# Drone_v1_0.net
KiCad netlist of a schematic drawn in Altium Designer
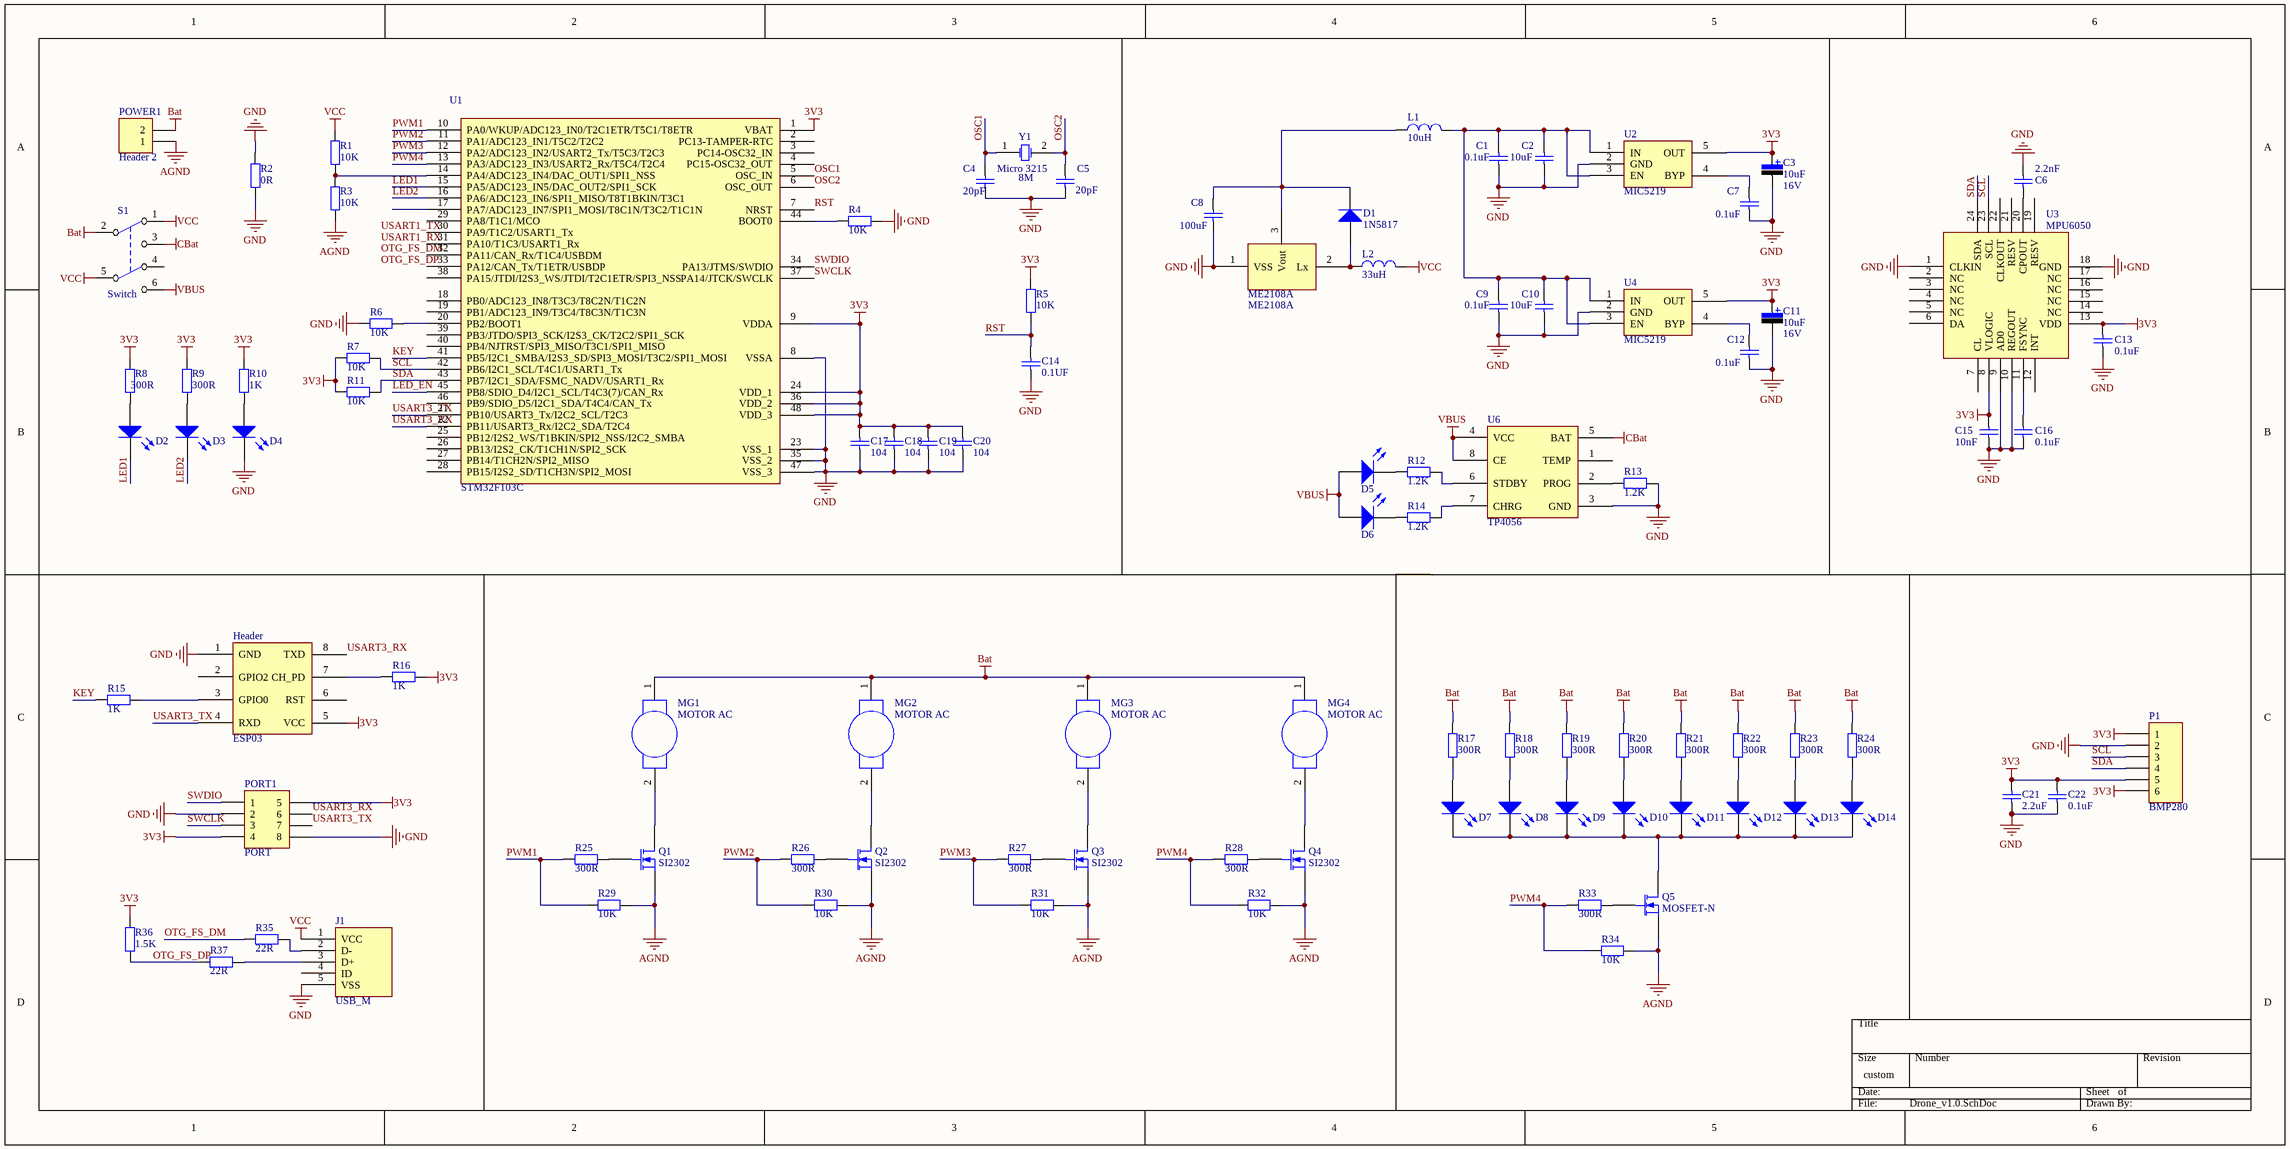
[diagram p0: Drone_v1.0.SchDoc]

(export (version "E")
  (design (tool "Eeschema 10.0.6"))
  (components
    (comp (ref "C1")
      (value "0.1uF")
      (footprint "0805-2")
      (description "Capacitor")
      (fields (field (name "Comment") "0402 12pF") (field (name "PUBLISHER") "Altium Limited"))
      (libsource (lib "Miscellaneous Devices") (part "Cap"))
    )
    (comp (ref "C2")
      (value "10uF")
      (footprint "0805-2")
      (description "Capacitor")
      (fields (field (name "Comment") "0402 12pF") (field (name "PUBLISHER") "Altium Limited"))
      (libsource (lib "Miscellaneous Devices") (part "Cap"))
    )
    (comp (ref "C3")
      (value "10uF")
      (footprint "CAP-3528")
      (description "极性电解电容")
      (fields
        (field (name "VOL") "16V")
        (field (name "Comment") "Cap Pol")
        (field (name "PUBLISHER") "Altium Limited")
      )
      (libsource (lib "Fszhang") (part "Cap Pol"))
    )
    (comp (ref "C4")
      (value "20pF")
      (footprint "0805-2")
      (description "Capacitor")
      (fields (field (name "Comment") "0402 12pF") (field (name "PUBLISHER") "Altium Limited"))
      (libsource (lib "Miscellaneous Devices") (part "Cap"))
    )
    (comp (ref "C5")
      (value "20pF")
      (footprint "0805-2")
      (description "Capacitor")
      (fields (field (name "Comment") "0402 12pF") (field (name "PUBLISHER") "Altium Limited"))
      (libsource (lib "Miscellaneous Devices") (part "Cap"))
    )
    (comp (ref "C6")
      (value "0402 12pF")
      (footprint "0805-2")
      (description "Capacitor")
      (fields (field (name "50V") "2.2nF") (field (name "PUBLISHER") "Altium Limited"))
      (libsource (lib "Miscellaneous Devices") (part "Cap"))
    )
    (comp (ref "C7")
      (value "0402 12pF")
      (footprint "0805-2")
      (description "Capacitor")
      (fields (field (name "50V") "0.1uF") (field (name "PUBLISHER") "Altium Limited"))
      (libsource (lib "Miscellaneous Devices") (part "Cap"))
    )
    (comp (ref "C8")
      (value "100uF")
      (footprint "0805-2")
      (description "Capacitor")
      (fields (field (name "Comment") "0402 12pF") (field (name "PUBLISHER") "Altium Limited"))
      (libsource (lib "Miscellaneous Devices") (part "Cap"))
    )
    (comp (ref "C9")
      (value "0.1uF")
      (footprint "0805-2")
      (description "Capacitor")
      (fields (field (name "Comment") "0402 12pF") (field (name "PUBLISHER") "Altium Limited"))
      (libsource (lib "Miscellaneous Devices") (part "Cap"))
    )
    (comp (ref "C10")
      (value "10uF")
      (footprint "0805-2")
      (description "Capacitor")
      (fields (field (name "Comment") "0402 12pF") (field (name "PUBLISHER") "Altium Limited"))
      (libsource (lib "Miscellaneous Devices") (part "Cap"))
    )
    (comp (ref "C11")
      (value "10uF")
      (footprint "CAP-3528")
      (description "极性电解电容")
      (fields
        (field (name "VOL") "16V")
        (field (name "Comment") "Cap Pol")
        (field (name "PUBLISHER") "Altium Limited")
      )
      (libsource (lib "Fszhang") (part "Cap Pol"))
    )
    (comp (ref "C12")
      (value "0402 12pF")
      (footprint "0805-2")
      (description "Capacitor")
      (fields (field (name "50V") "0.1uF") (field (name "PUBLISHER") "Altium Limited"))
      (libsource (lib "Miscellaneous Devices") (part "Cap"))
    )
    (comp (ref "C13")
      (value "0402 12pF")
      (footprint "0805-2")
      (description "Capacitor")
      (fields (field (name "50V") "0.1uF") (field (name "PUBLISHER") "Altium Limited"))
      (libsource (lib "Miscellaneous Devices") (part "Cap"))
    )
    (comp (ref "C14")
      (value "0.1UF")
      (footprint "0805-2")
      (description "无极性电容")
      (fields (field (name "Comment") "Cap") (field (name "PUBLISHER") "Altium Limited"))
      (libsource (lib "Fszhang") (part "Cap"))
    )
    (comp (ref "C15")
      (value "0402 12pF")
      (footprint "0805-2")
      (description "Capacitor")
      (fields (field (name "50V") "10nF") (field (name "PUBLISHER") "Altium Limited"))
      (libsource (lib "Miscellaneous Devices") (part "Cap"))
    )
    (comp (ref "C16")
      (value "0402 12pF")
      (footprint "0805-2")
      (description "Capacitor")
      (fields (field (name "50V") "0.1uF") (field (name "PUBLISHER") "Altium Limited"))
      (libsource (lib "Miscellaneous Devices") (part "Cap"))
    )
    (comp (ref "C17")
      (value "104")
      (footprint "0805-2")
      (description "无极性电容")
      (fields (field (name "Comment") "Cap") (field (name "PUBLISHER") "Altium Limited"))
      (libsource (lib "Fszhang") (part "Cap"))
    )
    (comp (ref "C18")
      (value "104")
      (footprint "0805-2")
      (description "无极性电容")
      (fields (field (name "Comment") "Cap") (field (name "PUBLISHER") "Altium Limited"))
      (libsource (lib "Fszhang") (part "Cap"))
    )
    (comp (ref "C19")
      (value "104")
      (footprint "0805-2")
      (description "无极性电容")
      (fields (field (name "Comment") "Cap") (field (name "PUBLISHER") "Altium Limited"))
      (libsource (lib "Fszhang") (part "Cap"))
    )
    (comp (ref "C20")
      (value "104")
      (footprint "0805-2")
      (description "无极性电容")
      (fields (field (name "Comment") "Cap") (field (name "PUBLISHER") "Altium Limited"))
      (libsource (lib "Fszhang") (part "Cap"))
    )
    (comp (ref "C21")
      (value "0402 12pF")
      (footprint "0805-2")
      (description "Capacitor")
      (fields (field (name "50V") "2.2uF") (field (name "PUBLISHER") "Altium Limited"))
      (libsource (lib "Miscellaneous Devices") (part "Cap"))
    )
    (comp (ref "C22")
      (value "0402 12pF")
      (footprint "0805-2")
      (description "Capacitor")
      (fields (field (name "50V") "0.1uF") (field (name "PUBLISHER") "Altium Limited"))
      (libsource (lib "Miscellaneous Devices") (part "Cap"))
    )
    (comp (ref "D1")
      (value "Diode")
      (footprint "DIODE-1206")
      (description "二极管")
      (fields (field (name "TYPE") "1N5817") (field (name "PUBLISHER") "Altium Limited"))
      (libsource (lib "Fszhang") (part "Diode"))
    )
    (comp (ref "D2")
      (value "LED0")
      (footprint "LED_0805")
      (description "发光二极管")
      (fields (field (name "PUBLISHER") "Altium Limited"))
      (libsource (lib "Fszhang") (part "LED0"))
    )
    (comp (ref "D3")
      (value "LED0")
      (footprint "LED_0805")
      (description "发光二极管")
      (fields (field (name "PUBLISHER") "Altium Limited"))
      (libsource (lib "Fszhang") (part "LED0"))
    )
    (comp (ref "D4")
      (value "LED0")
      (footprint "LED_0805")
      (description "发光二极管")
      (fields (field (name "PUBLISHER") "Altium Limited"))
      (libsource (lib "Fszhang") (part "LED0"))
    )
    (comp (ref "D5")
      (value "LED0")
      (footprint "LED_0805")
      (description "发光二极管")
      (fields (field (name "PUBLISHER") "Altium Limited"))
      (libsource (lib "Fszhang") (part "LED0"))
    )
    (comp (ref "D6")
      (value "LED0")
      (footprint "LED_0805")
      (description "发光二极管")
      (fields (field (name "PUBLISHER") "Altium Limited"))
      (libsource (lib "Fszhang") (part "LED0"))
    )
    (comp (ref "D7")
      (value "LED0")
      (footprint "LED_0805")
      (description "发光二极管")
      (fields (field (name "PUBLISHER") "Altium Limited"))
      (libsource (lib "Fszhang") (part "LED0"))
    )
    (comp (ref "D8")
      (value "LED0")
      (footprint "LED_0805")
      (description "发光二极管")
      (fields (field (name "PUBLISHER") "Altium Limited"))
      (libsource (lib "Fszhang") (part "LED0"))
    )
    (comp (ref "D9")
      (value "LED0")
      (footprint "LED_0805")
      (description "发光二极管")
      (fields (field (name "PUBLISHER") "Altium Limited"))
      (libsource (lib "Fszhang") (part "LED0"))
    )
    (comp (ref "D10")
      (value "LED0")
      (footprint "LED_0805")
      (description "发光二极管")
      (fields (field (name "PUBLISHER") "Altium Limited"))
      (libsource (lib "Fszhang") (part "LED0"))
    )
    (comp (ref "D11")
      (value "LED0")
      (footprint "LED_0805")
      (description "发光二极管")
      (fields (field (name "PUBLISHER") "Altium Limited"))
      (libsource (lib "Fszhang") (part "LED0"))
    )
    (comp (ref "D12")
      (value "LED0")
      (footprint "LED_0805")
      (description "发光二极管")
      (fields (field (name "PUBLISHER") "Altium Limited"))
      (libsource (lib "Fszhang") (part "LED0"))
    )
    (comp (ref "D13")
      (value "LED0")
      (footprint "LED_0805")
      (description "发光二极管")
      (fields (field (name "PUBLISHER") "Altium Limited"))
      (libsource (lib "Fszhang") (part "LED0"))
    )
    (comp (ref "D14")
      (value "LED0")
      (footprint "LED_0805")
      (description "发光二极管")
      (fields (field (name "PUBLISHER") "Altium Limited"))
      (libsource (lib "Fszhang") (part "LED0"))
    )
    (comp (ref "Header")
      (value "ESP03")
      (footprint "PCBComponent_1")
      (libsource (lib "Header4") (part "Hearder"))
    )
    (comp (ref "J1")
      (value "USB_M")
      (footprint "USB_MICRO")
      (description "MicroUSB接口")
      (libsource (lib "Fszhang") (part "USB_M"))
    )
    (comp (ref "L1")
      (value "10uH")
      (footprint "0805-1")
      (description "电感")
      (fields (field (name "Comment") "Inductor") (field (name "PUBLISHER") "Altium Limited"))
      (libsource (lib "Fszhang") (part "Inductor"))
    )
    (comp (ref "L2")
      (value "33uH")
      (footprint "0805-1")
      (description "电感")
      (fields (field (name "Comment") "Inductor") (field (name "PUBLISHER") "Altium Limited"))
      (libsource (lib "Fszhang") (part "Inductor"))
    )
    (comp (ref "ME2108A") (value "ME2108A") (libsource (lib "ME2108A") (part "ME2108A")))
    (comp (ref "MG1") (value "MOTOR AC") (footprint "Motor") (libsource (lib "杂元件库") (part "MOTOR AC")))
    (comp (ref "MG2") (value "MOTOR AC") (footprint "Motor") (libsource (lib "杂元件库") (part "MOTOR AC")))
    (comp (ref "MG3") (value "MOTOR AC") (footprint "Motor") (libsource (lib "杂元件库") (part "MOTOR AC")))
    (comp (ref "MG4") (value "MOTOR AC") (footprint "Motor") (libsource (lib "杂元件库") (part "MOTOR AC")))
    (comp (ref "P1")
      (value "BMP280")
      (footprint "HDR1X6")
      (description "Header, 6-Pin")
      (fields (field (name "PUBLISHER") "Altium Limited"))
      (libsource (lib "Miscellaneous Connectors") (part "Header 6"))
    )
    (comp (ref "PORT1")
      (value "PORT")
      (footprint "HDR2X4_CEN")
      (description "Header, 4-Pin, Dual row")
      (fields (field (name "PUBLISHER") "Altium Limited"))
      (libsource (lib "Miscellaneous Connectors") (part "Header 4X2A"))
    )
    (comp (ref "POWER1")
      (value "Header 2")
      (footprint "HDR1X2")
      (description "Header, 2-Pin")
      (fields (field (name "PUBLISHER") "Altium Limited"))
      (libsource (lib "Miscellaneous Connectors") (part "Header 2"))
    )
    (comp (ref "Q1")
      (value "SI2302")
      (footprint "SOT-23")
      (description "N-Channel MOSFET")
      (fields (field (name "PUBLISHER") "Altium Limited"))
      (libsource (lib "Miscellaneous Devices") (part "MOSFET-N"))
    )
    (comp (ref "Q2")
      (value "SI2302")
      (footprint "SOT-23")
      (description "N-Channel MOSFET")
      (fields (field (name "PUBLISHER") "Altium Limited"))
      (libsource (lib "Miscellaneous Devices") (part "MOSFET-N"))
    )
    (comp (ref "Q3")
      (value "SI2302")
      (footprint "SOT-23")
      (description "N-Channel MOSFET")
      (fields (field (name "PUBLISHER") "Altium Limited"))
      (libsource (lib "Miscellaneous Devices") (part "MOSFET-N"))
    )
    (comp (ref "Q4")
      (value "SI2302")
      (footprint "SOT-23")
      (description "N-Channel MOSFET")
      (fields (field (name "PUBLISHER") "Altium Limited"))
      (libsource (lib "Miscellaneous Devices") (part "MOSFET-N"))
    )
    (comp (ref "Q5")
      (value "MOSFET-N")
      (footprint "SOT-23")
      (description "N-Channel MOSFET")
      (fields (field (name "PUBLISHER") "Altium Limited"))
      (libsource (lib "Miscellaneous Devices") (part "MOSFET-N"))
    )
    (comp (ref "R1")
      (value "10K")
      (footprint "0805-2")
      (description "贴片电阻")
      (fields (field (name "Comment") "Res1") (field (name "PUBLISHER") "Altium Limited"))
      (libsource (lib "Fszhang") (part "Res1"))
    )
    (comp (ref "R2")
      (value "0R")
      (footprint "0805-2")
      (description "贴片电阻")
      (fields (field (name "Comment") "Res1") (field (name "PUBLISHER") "Altium Limited"))
      (libsource (lib "Fszhang") (part "Res1"))
    )
    (comp (ref "R3")
      (value "10K")
      (footprint "0805-2")
      (description "贴片电阻")
      (fields (field (name "Comment") "Res1") (field (name "PUBLISHER") "Altium Limited"))
      (libsource (lib "") (part "Res1_1"))
    )
    (comp (ref "R4")
      (value "10K")
      (footprint "0805-2")
      (description "贴片电阻")
      (fields (field (name "Comment") "Res1") (field (name "PUBLISHER") "Altium Limited"))
      (libsource (lib "") (part "Res1_3"))
    )
    (comp (ref "R5")
      (value "10K")
      (footprint "0805-2")
      (description "贴片电阻")
      (fields (field (name "Comment") "Res1") (field (name "PUBLISHER") "Altium Limited"))
      (libsource (lib "Fszhang") (part "Res1"))
    )
    (comp (ref "R6")
      (value "10K")
      (footprint "0805-2")
      (description "贴片电阻")
      (fields (field (name "Comment") "Res1") (field (name "PUBLISHER") "Altium Limited"))
      (libsource (lib "") (part "Res1_2"))
    )
    (comp (ref "R7")
      (value "10K")
      (footprint "0805-2")
      (description "贴片电阻")
      (fields (field (name "Comment") "Res1") (field (name "PUBLISHER") "Altium Limited"))
      (libsource (lib "") (part "Res1_2"))
    )
    (comp (ref "R8")
      (value "300R")
      (footprint "0805-2")
      (description "贴片电阻")
      (fields (field (name "Comment") "Res1") (field (name "PUBLISHER") "Altium Limited"))
      (libsource (lib "Fszhang") (part "Res1"))
    )
    (comp (ref "R9")
      (value "300R")
      (footprint "0805-2")
      (description "贴片电阻")
      (fields (field (name "Comment") "Res1") (field (name "PUBLISHER") "Altium Limited"))
      (libsource (lib "Fszhang") (part "Res1"))
    )
    (comp (ref "R10")
      (value "1K")
      (footprint "0805-2")
      (description "贴片电阻")
      (fields (field (name "Comment") "Res1") (field (name "PUBLISHER") "Altium Limited"))
      (libsource (lib "Fszhang") (part "Res1"))
    )
    (comp (ref "R11")
      (value "10K")
      (footprint "0805-2")
      (description "贴片电阻")
      (fields (field (name "Comment") "Res1") (field (name "PUBLISHER") "Altium Limited"))
      (libsource (lib "") (part "Res1_2"))
    )
    (comp (ref "R12")
      (value "1.2K")
      (footprint "0805-2")
      (description "贴片电阻")
      (fields (field (name "Comment") "Res1") (field (name "PUBLISHER") "Altium Limited"))
      (libsource (lib "") (part "Res1_3"))
    )
    (comp (ref "R13")
      (value "1.2K")
      (footprint "0805-2")
      (description "贴片电阻")
      (fields (field (name "Comment") "Res1") (field (name "PUBLISHER") "Altium Limited"))
      (libsource (lib "") (part "Res1_3"))
    )
    (comp (ref "R14")
      (value "1.2K")
      (footprint "0805-2")
      (description "贴片电阻")
      (fields (field (name "Comment") "Res1") (field (name "PUBLISHER") "Altium Limited"))
      (libsource (lib "") (part "Res1_3"))
    )
    (comp (ref "R15")
      (value "1K")
      (footprint "0805-2")
      (description "贴片电阻")
      (fields (field (name "Comment") "Res1") (field (name "PUBLISHER") "Altium Limited"))
      (libsource (lib "") (part "Res1_2"))
    )
    (comp (ref "R16")
      (value "1K")
      (footprint "0805-2")
      (description "贴片电阻")
      (fields (field (name "Comment") "Res1") (field (name "PUBLISHER") "Altium Limited"))
      (libsource (lib "") (part "Res1_2"))
    )
    (comp (ref "R17")
      (value "300R")
      (footprint "0805-2")
      (description "贴片电阻")
      (fields (field (name "Comment") "Res1") (field (name "PUBLISHER") "Altium Limited"))
      (libsource (lib "") (part "Res1_1"))
    )
    (comp (ref "R18")
      (value "300R")
      (footprint "0805-2")
      (description "贴片电阻")
      (fields (field (name "Comment") "Res1") (field (name "PUBLISHER") "Altium Limited"))
      (libsource (lib "") (part "Res1_1"))
    )
    (comp (ref "R19")
      (value "300R")
      (footprint "0805-2")
      (description "贴片电阻")
      (fields (field (name "Comment") "Res1") (field (name "PUBLISHER") "Altium Limited"))
      (libsource (lib "") (part "Res1_1"))
    )
    (comp (ref "R20")
      (value "300R")
      (footprint "0805-2")
      (description "贴片电阻")
      (fields (field (name "Comment") "Res1") (field (name "PUBLISHER") "Altium Limited"))
      (libsource (lib "") (part "Res1_1"))
    )
    (comp (ref "R21")
      (value "300R")
      (footprint "0805-2")
      (description "贴片电阻")
      (fields (field (name "Comment") "Res1") (field (name "PUBLISHER") "Altium Limited"))
      (libsource (lib "") (part "Res1_1"))
    )
    (comp (ref "R22")
      (value "300R")
      (footprint "0805-2")
      (description "贴片电阻")
      (fields (field (name "Comment") "Res1") (field (name "PUBLISHER") "Altium Limited"))
      (libsource (lib "") (part "Res1_1"))
    )
    (comp (ref "R23")
      (value "300R")
      (footprint "0805-2")
      (description "贴片电阻")
      (fields (field (name "Comment") "Res1") (field (name "PUBLISHER") "Altium Limited"))
      (libsource (lib "") (part "Res1_1"))
    )
    (comp (ref "R24")
      (value "300R")
      (footprint "0805-2")
      (description "贴片电阻")
      (fields (field (name "Comment") "Res1") (field (name "PUBLISHER") "Altium Limited"))
      (libsource (lib "") (part "Res1_1"))
    )
    (comp (ref "R25")
      (value "300R")
      (footprint "0805-2")
      (description "贴片电阻")
      (fields (field (name "Comment") "Res1") (field (name "PUBLISHER") "Altium Limited"))
      (libsource (lib "") (part "Res1_3"))
    )
    (comp (ref "R26")
      (value "300R")
      (footprint "0805-2")
      (description "贴片电阻")
      (fields (field (name "Comment") "Res1") (field (name "PUBLISHER") "Altium Limited"))
      (libsource (lib "") (part "Res1_3"))
    )
    (comp (ref "R27")
      (value "300R")
      (footprint "0805-2")
      (description "贴片电阻")
      (fields (field (name "Comment") "Res1") (field (name "PUBLISHER") "Altium Limited"))
      (libsource (lib "") (part "Res1_3"))
    )
    (comp (ref "R28")
      (value "300R")
      (footprint "0805-2")
      (description "贴片电阻")
      (fields (field (name "Comment") "Res1") (field (name "PUBLISHER") "Altium Limited"))
      (libsource (lib "") (part "Res1_3"))
    )
    (comp (ref "R29")
      (value "10K")
      (footprint "0805-2")
      (description "贴片电阻")
      (fields (field (name "Comment") "Res1") (field (name "PUBLISHER") "Altium Limited"))
      (libsource (lib "") (part "Res1_3"))
    )
    (comp (ref "R30")
      (value "10K")
      (footprint "0805-2")
      (description "贴片电阻")
      (fields (field (name "Comment") "Res1") (field (name "PUBLISHER") "Altium Limited"))
      (libsource (lib "") (part "Res1_3"))
    )
    (comp (ref "R31")
      (value "10K")
      (footprint "0805-2")
      (description "贴片电阻")
      (fields (field (name "Comment") "Res1") (field (name "PUBLISHER") "Altium Limited"))
      (libsource (lib "") (part "Res1_3"))
    )
    (comp (ref "R32")
      (value "10K")
      (footprint "0805-2")
      (description "贴片电阻")
      (fields (field (name "Comment") "Res1") (field (name "PUBLISHER") "Altium Limited"))
      (libsource (lib "") (part "Res1_3"))
    )
    (comp (ref "R33")
      (value "300R")
      (footprint "0805-2")
      (description "贴片电阻")
      (fields (field (name "Comment") "Res1") (field (name "PUBLISHER") "Altium Limited"))
      (libsource (lib "") (part "Res1_3"))
    )
    (comp (ref "R34")
      (value "10K")
      (footprint "0805-2")
      (description "贴片电阻")
      (fields (field (name "Comment") "Res1") (field (name "PUBLISHER") "Altium Limited"))
      (libsource (lib "") (part "Res1_3"))
    )
    (comp (ref "R35")
      (value "22R")
      (footprint "0805-2")
      (description "贴片电阻")
      (fields (field (name "Comment") "Res1") (field (name "PUBLISHER") "Altium Limited"))
      (libsource (lib "") (part "Res1_2"))
    )
    (comp (ref "R36")
      (value "1.5K")
      (footprint "0805-2")
      (description "贴片电阻")
      (fields (field (name "Comment") "Res1") (field (name "PUBLISHER") "Altium Limited"))
      (libsource (lib "Fszhang") (part "Res1"))
    )
    (comp (ref "R37")
      (value "22R")
      (footprint "0805-2")
      (description "贴片电阻")
      (fields (field (name "Comment") "Res1") (field (name "PUBLISHER") "Altium Limited"))
      (libsource (lib "") (part "Res1_2"))
    )
    (comp (ref "S1") (value "Switch") (footprint "开关") (libsource (lib "开关") (part "双刀双柄开关")))
    (comp (ref "U1")
      (value "STM32F103C")
      (footprint "LQFP-48_M")
      (description "STM32单片机48引脚")
      (libsource (lib "Fszhang") (part "STM32F103C"))
    )
    (comp (ref "U2") (value "MIC5219") (footprint "SOT25-5") (libsource (lib "MIC5219") (part "MIC5219")))
    (comp (ref "U3")
      (value "MPU6050")
      (footprint "QFN50P400X400X90-24N")
      (libsource (lib "MPU6050") (part "MPU6050"))
    )
    (comp (ref "U4") (value "MIC5219") (footprint "SOT25-5") (libsource (lib "MIC5219") (part "MIC5219")))
    (comp (ref "U6") (value "TP4056") (footprint "SOP8") (libsource (lib "TP4056") (part "TP4056")))
    (comp (ref "Y1")
      (value "Micro 3215")
      (footprint "SMDXTAL3225")
      (description "Crystal Oscillator")
      (fields (field (name "ALTIUM_VALUE") "8M"))
      (libsource (lib "Miscellaneous Devices") (part "XTAL"))
    )
  )
  (nets
    (net (code "1") (name "/KEY") (class "Default")
      (node (ref "R15") (pin "1") (pinfunction "1_1") (pintype "passive"))
      (node (ref "U1") (pin "41") (pinfunction "PB5/I2C1_SMBA/I2S3_SD/SPI3_MOSI/T3C2/SPI1_MOSI_41") (pintype "passive"))
    )
    (net (code "2") (name "/LED1") (class "Default")
      (node (ref "D2") (pin "2") (pinfunction "K_2") (pintype "passive"))
      (node (ref "U1") (pin "15") (pinfunction "PA5/ADC123_IN5/DAC_OUT2/SPI1_SCK_15") (pintype "passive"))
    )
    (net (code "3") (name "/LED2") (class "Default")
      (node (ref "D3") (pin "2") (pinfunction "K_2") (pintype "passive"))
      (node (ref "U1") (pin "16") (pinfunction "PA6/ADC123_IN6/SPI1_MISO/T8T1BKIN/T3C1_16") (pintype "passive"))
    )
    (net (code "4") (name "/LED_EN") (class "Default")
      (node (ref "U1") (pin "45") (pinfunction "PB8/SDIO_D4/I2C1_SCL/T4C3(7)/CAN_Rx_45") (pintype "passive"))
    )
    (net (code "5") (name "/OSC1") (class "Default")
      (node (ref "C4") (pin "1") (pinfunction "1_1") (pintype "passive"))
      (node (ref "U1") (pin "5") (pinfunction "OSC_IN_5") (pintype "passive"))
      (node (ref "Y1") (pin "1") (pinfunction "OSC1_1") (pintype "passive"))
    )
    (net (code "6") (name "/OSC2") (class "Default")
      (node (ref "C5") (pin "2") (pinfunction "2_2") (pintype "passive"))
      (node (ref "U1") (pin "6") (pinfunction "OSC_OUT_6") (pintype "passive"))
      (node (ref "Y1") (pin "2") (pinfunction "OSC2_2") (pintype "passive"))
    )
    (net (code "7") (name "/OTG_FS_DM") (class "Default")
      (node (ref "R35") (pin "1") (pinfunction "1_1") (pintype "passive"))
    )
    (net (code "8") (name "/OTG_FS_DP") (class "Default")
      (node (ref "R36") (pin "1") (pinfunction "1_1") (pintype "passive"))
      (node (ref "R37") (pin "1") (pinfunction "1_1") (pintype "passive"))
    )
    (net (code "9") (name "/PWM1") (class "Default")
      (node (ref "R25") (pin "2") (pinfunction "2_2") (pintype "passive"))
      (node (ref "R29") (pin "2") (pinfunction "2_2") (pintype "passive"))
      (node (ref "U1") (pin "10") (pinfunction "PA0/WKUP/ADC123_IN0/T2C1ETR/T5C1/T8ETR_10") (pintype "passive"))
    )
    (net (code "10") (name "/PWM2") (class "Default")
      (node (ref "R26") (pin "2") (pinfunction "2_2") (pintype "passive"))
      (node (ref "R30") (pin "2") (pinfunction "2_2") (pintype "passive"))
      (node (ref "U1") (pin "11") (pinfunction "PA1/ADC123_IN1/T5C2/T2C2_11") (pintype "passive"))
    )
    (net (code "11") (name "/PWM3") (class "Default")
      (node (ref "R27") (pin "2") (pinfunction "2_2") (pintype "passive"))
      (node (ref "R31") (pin "2") (pinfunction "2_2") (pintype "passive"))
      (node (ref "U1") (pin "12") (pinfunction "PA2/ADC123_IN2/USART2_Tx/T5C3/T2C3_12") (pintype "passive"))
    )
    (net (code "12") (name "/PWM4") (class "Default")
      (node (ref "R28") (pin "2") (pinfunction "2_2") (pintype "passive"))
      (node (ref "R32") (pin "2") (pinfunction "2_2") (pintype "passive"))
      (node (ref "R33") (pin "2") (pinfunction "2_2") (pintype "passive"))
      (node (ref "R34") (pin "2") (pinfunction "2_2") (pintype "passive"))
      (node (ref "U1") (pin "13") (pinfunction "PA3/ADC123_IN3/USART2_Rx/T5C4/T2C4_13") (pintype "passive"))
    )
    (net (code "13") (name "/RST") (class "Default")
      (node (ref "C14") (pin "1") (pinfunction "1_1") (pintype "passive"))
      (node (ref "R5") (pin "1") (pinfunction "1_1") (pintype "passive"))
      (node (ref "U1") (pin "7") (pinfunction "NRST_7") (pintype "passive"))
    )
    (net (code "14") (name "/SCL") (class "Default")
      (node (ref "P1") (pin "3") (pinfunction "3_3") (pintype "passive"))
      (node (ref "R7") (pin "2") (pinfunction "2_2") (pintype "passive"))
      (node (ref "U1") (pin "42") (pinfunction "PB6/I2C1_SCL/T4C1/USART1_Tx_42") (pintype "passive"))
      (node (ref "U3") (pin "23") (pinfunction "SCL_23") (pintype "passive"))
    )
    (net (code "15") (name "/SDA") (class "Default")
      (node (ref "P1") (pin "4") (pinfunction "4_4") (pintype "passive"))
      (node (ref "R11") (pin "2") (pinfunction "2_2") (pintype "passive"))
      (node (ref "U1") (pin "43") (pinfunction "PB7/I2C1_SDA/FSMC_NADV/USART1_Rx_43") (pintype "passive"))
      (node (ref "U3") (pin "24") (pinfunction "SDA_24") (pintype "passive"))
    )
    (net (code "16") (name "/SWCLK") (class "Default")
      (node (ref "PORT1") (pin "3") (pinfunction "3_3") (pintype "passive"))
      (node (ref "U1") (pin "37") (pinfunction "PA14/JTCK/SWCLK_37") (pintype "passive"))
    )
    (net (code "17") (name "/SWDIO") (class "Default")
      (node (ref "PORT1") (pin "1") (pinfunction "1_1") (pintype "passive"))
      (node (ref "U1") (pin "34") (pinfunction "PA13/JTMS/SWDIO_34") (pintype "passive"))
    )
    (net (code "20") (name "/USART3_RX") (class "Default")
      (node (ref "Header") (pin "8") (pinfunction "TXD_8") (pintype "passive"))
      (node (ref "PORT1") (pin "6") (pinfunction "6_6") (pintype "passive"))
      (node (ref "U1") (pin "22") (pinfunction "PB11/USART3_Rx/I2C2_SDA/T2C4_22") (pintype "passive"))
    )
    (net (code "21") (name "/USART3_TX") (class "Default")
      (node (ref "Header") (pin "4") (pinfunction "RXD_4") (pintype "passive"))
      (node (ref "PORT1") (pin "7") (pinfunction "7_7") (pintype "passive"))
      (node (ref "U1") (pin "21") (pinfunction "PB10/USART3_Tx/I2C2_SCL/T2C3_21") (pintype "passive"))
    )
    (net (code "22") (name "3V3") (class "Default")
      (node (ref "C11") (pin "1") (pinfunction "1_1") (pintype "passive"))
      (node (ref "C13") (pin "1") (pinfunction "1_1") (pintype "passive"))
      (node (ref "C15") (pin "1") (pinfunction "1_1") (pintype "passive"))
      (node (ref "C17") (pin "2") (pinfunction "2_2") (pintype "passive"))
      (node (ref "C18") (pin "2") (pinfunction "2_2") (pintype "passive"))
      (node (ref "C19") (pin "2") (pinfunction "2_2") (pintype "passive"))
      (node (ref "C20") (pin "2") (pinfunction "2_2") (pintype "passive"))
      (node (ref "C21") (pin "1") (pinfunction "1_1") (pintype "passive"))
      (node (ref "C22") (pin "1") (pinfunction "1_1") (pintype "passive"))
      (node (ref "C3") (pin "1") (pinfunction "1_1") (pintype "passive"))
      (node (ref "Header") (pin "5") (pinfunction "VCC_5") (pintype "passive"))
      (node (ref "P1") (pin "1") (pinfunction "1_1") (pintype "passive"))
      (node (ref "P1") (pin "5") (pinfunction "5_5") (pintype "passive"))
      (node (ref "P1") (pin "6") (pinfunction "6_6") (pintype "passive"))
      (node (ref "PORT1") (pin "4") (pinfunction "4_4") (pintype "passive"))
      (node (ref "PORT1") (pin "5") (pinfunction "5_5") (pintype "passive"))
      (node (ref "R10") (pin "2") (pinfunction "2_2") (pintype "passive"))
      (node (ref "R11") (pin "1") (pinfunction "1_1") (pintype "passive"))
      (node (ref "R16") (pin "2") (pinfunction "2_2") (pintype "passive"))
      (node (ref "R36") (pin "2") (pinfunction "2_2") (pintype "passive"))
      (node (ref "R5") (pin "2") (pinfunction "2_2") (pintype "passive"))
      (node (ref "R7") (pin "1") (pinfunction "1_1") (pintype "passive"))
      (node (ref "R8") (pin "2") (pinfunction "2_2") (pintype "passive"))
      (node (ref "R9") (pin "2") (pinfunction "2_2") (pintype "passive"))
      (node (ref "U1") (pin "1") (pinfunction "VBAT_1") (pintype "passive"))
      (node (ref "U1") (pin "24") (pinfunction "VDD_1_24") (pintype "passive"))
      (node (ref "U1") (pin "36") (pinfunction "VDD_2_36") (pintype "passive"))
      (node (ref "U1") (pin "48") (pinfunction "VDD_3_48") (pintype "passive"))
      (node (ref "U1") (pin "9") (pinfunction "VDDA_9") (pintype "passive"))
      (node (ref "U2") (pin "5") (pinfunction "OUT_5") (pintype "passive"))
      (node (ref "U3") (pin "13") (pinfunction "VDD_13") (pintype "passive"))
      (node (ref "U3") (pin "8") (pinfunction "VLOGIC_8") (pintype "passive"))
      (node (ref "U4") (pin "5") (pinfunction "OUT_5") (pintype "passive"))
    )
    (net (code "23") (name "AGND") (class "Default")
      (node (ref "POWER1") (pin "1") (pinfunction "1_1") (pintype "passive"))
      (node (ref "Q1") (pin "3") (pinfunction "S_3") (pintype "passive"))
      (node (ref "Q2") (pin "3") (pinfunction "S_3") (pintype "passive"))
      (node (ref "Q3") (pin "3") (pinfunction "S_3") (pintype "passive"))
      (node (ref "Q4") (pin "3") (pinfunction "S_3") (pintype "passive"))
      (node (ref "Q5") (pin "3") (pinfunction "S_3") (pintype "passive"))
      (node (ref "R29") (pin "1") (pinfunction "1_1") (pintype "passive"))
      (node (ref "R3") (pin "2") (pinfunction "2_2") (pintype "passive"))
      (node (ref "R30") (pin "1") (pinfunction "1_1") (pintype "passive"))
      (node (ref "R31") (pin "1") (pinfunction "1_1") (pintype "passive"))
      (node (ref "R32") (pin "1") (pinfunction "1_1") (pintype "passive"))
      (node (ref "R34") (pin "1") (pinfunction "1_1") (pintype "passive"))
    )
    (net (code "24") (name "Bat") (class "Default")
      (node (ref "MG1") (pin "1") (pinfunction "1_1") (pintype "passive"))
      (node (ref "MG2") (pin "1") (pinfunction "1_1") (pintype "passive"))
      (node (ref "MG3") (pin "1") (pinfunction "1_1") (pintype "passive"))
      (node (ref "MG4") (pin "1") (pinfunction "1_1") (pintype "passive"))
      (node (ref "POWER1") (pin "2") (pinfunction "2_2") (pintype "passive"))
      (node (ref "R17") (pin "1") (pinfunction "1_1") (pintype "passive"))
      (node (ref "R18") (pin "1") (pinfunction "1_1") (pintype "passive"))
      (node (ref "R19") (pin "1") (pinfunction "1_1") (pintype "passive"))
      (node (ref "R20") (pin "1") (pinfunction "1_1") (pintype "passive"))
      (node (ref "R21") (pin "1") (pinfunction "1_1") (pintype "passive"))
      (node (ref "R22") (pin "1") (pinfunction "1_1") (pintype "passive"))
      (node (ref "R23") (pin "1") (pinfunction "1_1") (pintype "passive"))
      (node (ref "R24") (pin "1") (pinfunction "1_1") (pintype "passive"))
      (node (ref "S1") (pin "2") (pinfunction "COMMON1_2") (pintype "passive"))
    )
    (net (code "25") (name "CBat") (class "Default")
      (node (ref "S1") (pin "3") (pinfunction "NO1_3") (pintype "passive"))
      (node (ref "U6") (pin "5") (pinfunction "BAT_5") (pintype "passive"))
    )
    (net (code "26") (name "GND") (class "Default")
      (node (ref "C1") (pin "2") (pinfunction "2_2") (pintype "passive"))
      (node (ref "C10") (pin "2") (pinfunction "2_2") (pintype "passive"))
      (node (ref "C11") (pin "2") (pinfunction "2_2") (pintype "passive"))
      (node (ref "C12") (pin "2") (pinfunction "2_2") (pintype "passive"))
      (node (ref "C13") (pin "2") (pinfunction "2_2") (pintype "passive"))
      (node (ref "C14") (pin "2") (pinfunction "2_2") (pintype "passive"))
      (node (ref "C15") (pin "2") (pinfunction "2_2") (pintype "passive"))
      (node (ref "C16") (pin "2") (pinfunction "2_2") (pintype "passive"))
      (node (ref "C17") (pin "1") (pinfunction "1_1") (pintype "passive"))
      (node (ref "C18") (pin "1") (pinfunction "1_1") (pintype "passive"))
      (node (ref "C19") (pin "1") (pinfunction "1_1") (pintype "passive"))
      (node (ref "C2") (pin "2") (pinfunction "2_2") (pintype "passive"))
      (node (ref "C20") (pin "1") (pinfunction "1_1") (pintype "passive"))
      (node (ref "C21") (pin "2") (pinfunction "2_2") (pintype "passive"))
      (node (ref "C22") (pin "2") (pinfunction "2_2") (pintype "passive"))
      (node (ref "C3") (pin "2") (pinfunction "2_2") (pintype "passive"))
      (node (ref "C4") (pin "2") (pinfunction "2_2") (pintype "passive"))
      (node (ref "C5") (pin "1") (pinfunction "1_1") (pintype "passive"))
      (node (ref "C6") (pin "1") (pinfunction "1_1") (pintype "passive"))
      (node (ref "C7") (pin "2") (pinfunction "2_2") (pintype "passive"))
      (node (ref "C8") (pin "2") (pinfunction "2_2") (pintype "passive"))
      (node (ref "C9") (pin "2") (pinfunction "2_2") (pintype "passive"))
      (node (ref "D4") (pin "2") (pinfunction "K_2") (pintype "passive"))
      (node (ref "Header") (pin "1") (pinfunction "GND_1") (pintype "passive"))
      (node (ref "J1") (pin "5") (pinfunction "VSS_5") (pintype "passive"))
      (node (ref "ME2108A") (pin "1") (pinfunction "VSS_1") (pintype "passive"))
      (node (ref "P1") (pin "2") (pinfunction "2_2") (pintype "passive"))
      (node (ref "PORT1") (pin "2") (pinfunction "2_2") (pintype "passive"))
      (node (ref "PORT1") (pin "8") (pinfunction "8_8") (pintype "passive"))
      (node (ref "R13") (pin "1") (pinfunction "1_1") (pintype "passive"))
      (node (ref "R2") (pin "1") (pinfunction "1_1") (pintype "passive"))
      (node (ref "R2") (pin "2") (pinfunction "2_2") (pintype "passive"))
      (node (ref "R4") (pin "1") (pinfunction "1_1") (pintype "passive"))
      (node (ref "R6") (pin "1") (pinfunction "1_1") (pintype "passive"))
      (node (ref "U1") (pin "23") (pinfunction "VSS_1_23") (pintype "passive"))
      (node (ref "U1") (pin "35") (pinfunction "VSS_2_35") (pintype "passive"))
      (node (ref "U1") (pin "47") (pinfunction "VSS_3_47") (pintype "passive"))
      (node (ref "U1") (pin "8") (pinfunction "VSSA_8") (pintype "passive"))
      (node (ref "U2") (pin "2") (pinfunction "GND_2") (pintype "passive"))
      (node (ref "U3") (pin "1") (pinfunction "CLKIN_1") (pintype "passive"))
      (node (ref "U3") (pin "10") (pinfunction "REGOUT_10") (pintype "passive"))
      (node (ref "U3") (pin "18") (pinfunction "GND_18") (pintype "passive"))
      (node (ref "U3") (pin "9") (pinfunction "AD0_9") (pintype "passive"))
      (node (ref "U4") (pin "2") (pinfunction "GND_2") (pintype "passive"))
      (node (ref "U6") (pin "3") (pinfunction "GND_3") (pintype "passive"))
    )
    (net (code "27") (name "Net-(D1-A)") (class "Default")
      (node (ref "D1") (pin "1") (pinfunction "A_1") (pintype "passive"))
      (node (ref "L2") (pin "1") (pinfunction "1_1") (pintype "passive"))
      (node (ref "ME2108A") (pin "2") (pinfunction "Lx_2") (pintype "passive"))
    )
    (net (code "28") (name "Net-(D1-K)") (class "Default")
      (node (ref "C8") (pin "1") (pinfunction "1_1") (pintype "passive"))
      (node (ref "D1") (pin "2") (pinfunction "K_2") (pintype "passive"))
      (node (ref "L1") (pin "1") (pinfunction "1_1") (pintype "passive"))
      (node (ref "ME2108A") (pin "3") (pinfunction "Vout_3") (pintype "passive"))
    )
    (net (code "29") (name "Net-(D2-A)") (class "Default")
      (node (ref "D2") (pin "1") (pinfunction "A_1") (pintype "passive"))
      (node (ref "R8") (pin "1") (pinfunction "1_1") (pintype "passive"))
    )
    (net (code "30") (name "Net-(D3-A)") (class "Default")
      (node (ref "D3") (pin "1") (pinfunction "A_1") (pintype "passive"))
      (node (ref "R9") (pin "1") (pinfunction "1_1") (pintype "passive"))
    )
    (net (code "31") (name "Net-(D4-A)") (class "Default")
      (node (ref "D4") (pin "1") (pinfunction "A_1") (pintype "passive"))
      (node (ref "R10") (pin "1") (pinfunction "1_1") (pintype "passive"))
    )
    (net (code "32") (name "Net-(D5-K)") (class "Default")
      (node (ref "D5") (pin "2") (pinfunction "K_2") (pintype "passive"))
      (node (ref "R12") (pin "2") (pinfunction "2_2") (pintype "passive"))
    )
    (net (code "33") (name "Net-(D6-K)") (class "Default")
      (node (ref "D6") (pin "2") (pinfunction "K_2") (pintype "passive"))
      (node (ref "R14") (pin "2") (pinfunction "2_2") (pintype "passive"))
    )
    (net (code "34") (name "Net-(D7-A)") (class "Default")
      (node (ref "D7") (pin "1") (pinfunction "A_1") (pintype "passive"))
      (node (ref "R17") (pin "2") (pinfunction "2_2") (pintype "passive"))
    )
    (net (code "35") (name "Net-(D8-A)") (class "Default")
      (node (ref "D8") (pin "1") (pinfunction "A_1") (pintype "passive"))
      (node (ref "R18") (pin "2") (pinfunction "2_2") (pintype "passive"))
    )
    (net (code "36") (name "Net-(D9-A)") (class "Default")
      (node (ref "D9") (pin "1") (pinfunction "A_1") (pintype "passive"))
      (node (ref "R19") (pin "2") (pinfunction "2_2") (pintype "passive"))
    )
    (net (code "37") (name "Net-(D10-A)") (class "Default")
      (node (ref "D10") (pin "1") (pinfunction "A_1") (pintype "passive"))
      (node (ref "R20") (pin "2") (pinfunction "2_2") (pintype "passive"))
    )
    (net (code "38") (name "Net-(D10-K)") (class "Default")
      (node (ref "D10") (pin "2") (pinfunction "K_2") (pintype "passive"))
      (node (ref "D11") (pin "2") (pinfunction "K_2") (pintype "passive"))
      (node (ref "D12") (pin "2") (pinfunction "K_2") (pintype "passive"))
      (node (ref "D13") (pin "2") (pinfunction "K_2") (pintype "passive"))
      (node (ref "D14") (pin "2") (pinfunction "K_2") (pintype "passive"))
      (node (ref "D7") (pin "2") (pinfunction "K_2") (pintype "passive"))
      (node (ref "D8") (pin "2") (pinfunction "K_2") (pintype "passive"))
      (node (ref "D9") (pin "2") (pinfunction "K_2") (pintype "passive"))
      (node (ref "Q5") (pin "1") (pinfunction "D_1") (pintype "passive"))
    )
    (net (code "39") (name "Net-(D11-A)") (class "Default")
      (node (ref "D11") (pin "1") (pinfunction "A_1") (pintype "passive"))
      (node (ref "R21") (pin "2") (pinfunction "2_2") (pintype "passive"))
    )
    (net (code "40") (name "Net-(D12-A)") (class "Default")
      (node (ref "D12") (pin "1") (pinfunction "A_1") (pintype "passive"))
      (node (ref "R22") (pin "2") (pinfunction "2_2") (pintype "passive"))
    )
    (net (code "41") (name "Net-(D13-A)") (class "Default")
      (node (ref "D13") (pin "1") (pinfunction "A_1") (pintype "passive"))
      (node (ref "R23") (pin "2") (pinfunction "2_2") (pintype "passive"))
    )
    (net (code "42") (name "Net-(D14-A)") (class "Default")
      (node (ref "D14") (pin "1") (pinfunction "A_1") (pintype "passive"))
      (node (ref "R24") (pin "2") (pinfunction "2_2") (pintype "passive"))
    )
    (net (code "43") (name "Net-(Header-CH_PD)") (class "Default")
      (node (ref "Header") (pin "7") (pinfunction "CH_PD_7") (pintype "passive"))
      (node (ref "R16") (pin "1") (pinfunction "1_1") (pintype "passive"))
    )
    (net (code "44") (name "Net-(Header-GPIO0)") (class "Default")
      (node (ref "Header") (pin "3") (pinfunction "GPIO0_3") (pintype "passive"))
      (node (ref "R15") (pin "2") (pinfunction "2_2") (pintype "passive"))
    )
    (net (code "45") (name "Net-(J1-D+)") (class "Default")
      (node (ref "J1") (pin "3") (pinfunction "D+_3") (pintype "passive"))
      (node (ref "R37") (pin "2") (pinfunction "2_2") (pintype "passive"))
    )
    (net (code "46") (name "Net-(J1-D-)") (class "Default")
      (node (ref "J1") (pin "2") (pinfunction "D-_2") (pintype "passive"))
      (node (ref "R35") (pin "2") (pinfunction "2_2") (pintype "passive"))
    )
    (net (code "47") (name "Net-(Q1-D)") (class "Default")
      (node (ref "MG1") (pin "2") (pinfunction "2_2") (pintype "passive"))
      (node (ref "Q1") (pin "1") (pinfunction "D_1") (pintype "passive"))
    )
    (net (code "48") (name "Net-(Q1-G)") (class "Default")
      (node (ref "Q1") (pin "2") (pinfunction "G_2") (pintype "passive"))
      (node (ref "R25") (pin "1") (pinfunction "1_1") (pintype "passive"))
    )
    (net (code "49") (name "Net-(Q2-D)") (class "Default")
      (node (ref "MG2") (pin "2") (pinfunction "2_2") (pintype "passive"))
      (node (ref "Q2") (pin "1") (pinfunction "D_1") (pintype "passive"))
    )
    (net (code "50") (name "Net-(Q2-G)") (class "Default")
      (node (ref "Q2") (pin "2") (pinfunction "G_2") (pintype "passive"))
      (node (ref "R26") (pin "1") (pinfunction "1_1") (pintype "passive"))
    )
    (net (code "51") (name "Net-(Q3-D)") (class "Default")
      (node (ref "MG3") (pin "2") (pinfunction "2_2") (pintype "passive"))
      (node (ref "Q3") (pin "1") (pinfunction "D_1") (pintype "passive"))
    )
    (net (code "52") (name "Net-(Q3-G)") (class "Default")
      (node (ref "Q3") (pin "2") (pinfunction "G_2") (pintype "passive"))
      (node (ref "R27") (pin "1") (pinfunction "1_1") (pintype "passive"))
    )
    (net (code "53") (name "Net-(Q4-D)") (class "Default")
      (node (ref "MG4") (pin "2") (pinfunction "2_2") (pintype "passive"))
      (node (ref "Q4") (pin "1") (pinfunction "D_1") (pintype "passive"))
    )
    (net (code "54") (name "Net-(Q4-G)") (class "Default")
      (node (ref "Q4") (pin "2") (pinfunction "G_2") (pintype "passive"))
      (node (ref "R28") (pin "1") (pinfunction "1_1") (pintype "passive"))
    )
    (net (code "55") (name "Net-(Q5-G)") (class "Default")
      (node (ref "Q5") (pin "2") (pinfunction "G_2") (pintype "passive"))
      (node (ref "R33") (pin "1") (pinfunction "1_1") (pintype "passive"))
    )
    (net (code "56") (name "Net-(U1-BOOT0)") (class "Default")
      (node (ref "R4") (pin "2") (pinfunction "2_2") (pintype "passive"))
      (node (ref "U1") (pin "44") (pinfunction "BOOT0_44") (pintype "passive"))
    )
    (net (code "57") (name "Net-(U1-PA4{slash}ADC123_IN4{slash}DAC_OUT1{slash}SPI1_NSS)") (class "Default")
      (node (ref "R1") (pin "1") (pinfunction "1_1") (pintype "passive"))
      (node (ref "R3") (pin "1") (pinfunction "1_1") (pintype "passive"))
      (node (ref "U1") (pin "14") (pinfunction "PA4/ADC123_IN4/DAC_OUT1/SPI1_NSS_14") (pintype "passive"))
    )
    (net (code "58") (name "Net-(U1-PB2{slash}BOOT1)") (class "Default")
      (node (ref "R6") (pin "2") (pinfunction "2_2") (pintype "passive"))
      (node (ref "U1") (pin "20") (pinfunction "PB2/BOOT1_20") (pintype "passive"))
    )
    (net (code "59") (name "Net-(U2-BYP)") (class "Default")
      (node (ref "C7") (pin "1") (pinfunction "1_1") (pintype "passive"))
      (node (ref "U2") (pin "4") (pinfunction "BYP_4") (pintype "passive"))
    )
    (net (code "60") (name "Net-(U2-EN)") (class "Default")
      (node (ref "C1") (pin "1") (pinfunction "1_1") (pintype "passive"))
      (node (ref "C10") (pin "1") (pinfunction "1_1") (pintype "passive"))
      (node (ref "C2") (pin "1") (pinfunction "1_1") (pintype "passive"))
      (node (ref "C9") (pin "1") (pinfunction "1_1") (pintype "passive"))
      (node (ref "L1") (pin "2") (pinfunction "2_2") (pintype "passive"))
      (node (ref "U2") (pin "1") (pinfunction "IN_1") (pintype "passive"))
      (node (ref "U2") (pin "3") (pinfunction "EN_3") (pintype "passive"))
      (node (ref "U4") (pin "1") (pinfunction "IN_1") (pintype "passive"))
      (node (ref "U4") (pin "3") (pinfunction "EN_3") (pintype "passive"))
    )
    (net (code "61") (name "Net-(U3-CPOUT)") (class "Default")
      (node (ref "C6") (pin "2") (pinfunction "2_2") (pintype "passive"))
      (node (ref "U3") (pin "20") (pinfunction "CPOUT_20") (pintype "passive"))
    )
    (net (code "62") (name "Net-(U3-FSYNC)") (class "Default")
      (node (ref "C16") (pin "1") (pinfunction "1_1") (pintype "passive"))
      (node (ref "U3") (pin "11") (pinfunction "FSYNC_11") (pintype "passive"))
    )
    (net (code "63") (name "Net-(U4-BYP)") (class "Default")
      (node (ref "C12") (pin "1") (pinfunction "1_1") (pintype "passive"))
      (node (ref "U4") (pin "4") (pinfunction "BYP_4") (pintype "passive"))
    )
    (net (code "64") (name "Net-(U6-CHRG)") (class "Default")
      (node (ref "R14") (pin "1") (pinfunction "1_1") (pintype "passive"))
      (node (ref "U6") (pin "7") (pinfunction "CHRG_7") (pintype "passive"))
    )
    (net (code "65") (name "Net-(U6-PROG)") (class "Default")
      (node (ref "R13") (pin "2") (pinfunction "2_2") (pintype "passive"))
      (node (ref "U6") (pin "2") (pinfunction "PROG_2") (pintype "passive"))
    )
    (net (code "66") (name "Net-(U6-STDBY)") (class "Default")
      (node (ref "R12") (pin "1") (pinfunction "1_1") (pintype "passive"))
      (node (ref "U6") (pin "6") (pinfunction "STDBY_6") (pintype "passive"))
    )
    (net (code "67") (name "VBUS") (class "Default")
      (node (ref "D5") (pin "1") (pinfunction "A_1") (pintype "passive"))
      (node (ref "D6") (pin "1") (pinfunction "A_1") (pintype "passive"))
      (node (ref "S1") (pin "6") (pinfunction "NO2_6") (pintype "passive"))
      (node (ref "U6") (pin "4") (pinfunction "VCC_4") (pintype "passive"))
      (node (ref "U6") (pin "8") (pinfunction "CE_8") (pintype "passive"))
    )
    (net (code "68") (name "VCC") (class "Default")
      (node (ref "J1") (pin "1") (pinfunction "VCC_1") (pintype "passive"))
      (node (ref "L2") (pin "2") (pinfunction "2_2") (pintype "passive"))
      (node (ref "R1") (pin "2") (pinfunction "2_2") (pintype "passive"))
      (node (ref "S1") (pin "1") (pinfunction "NC1_1") (pintype "passive"))
      (node (ref "S1") (pin "5") (pinfunction "COMMON2_5") (pintype "passive"))
    )
    (net (code "69") (name "unconnected-(Header-GPIO2-Pad2)") (class "Default")
      (node (ref "Header") (pin "2") (pinfunction "GPIO2_2") (pintype "passive"))
    )
    (net (code "70") (name "unconnected-(Header-RST-Pad6)") (class "Default")
      (node (ref "Header") (pin "6") (pinfunction "RST_6") (pintype "passive"))
    )
    (net (code "71") (name "unconnected-(J1-ID-Pad4)") (class "Default")
      (node (ref "J1") (pin "4") (pinfunction "ID_4") (pintype "passive"))
    )
    (net (code "72") (name "unconnected-(S1-NC2-Pad4)") (class "Default")
      (node (ref "S1") (pin "4") (pinfunction "NC2_4") (pintype "passive"))
    )
    (net (code "73") (name "unconnected-(U1-PA7{slash}ADC123_IN7{slash}SPI1_MOSI{slash}T8C1N{slash}T3C2{slash}T1C1N-Pad17)") (class "Default")
      (node (ref "U1") (pin "17") (pinfunction "PA7/ADC123_IN7/SPI1_MOSI/T8C1N/T3C2/T1C1N_17") (pintype "passive"))
    )
    (net (code "74") (name "unconnected-(U1-PA8{slash}T1C1{slash}MCO-Pad29)") (class "Default")
      (node (ref "U1") (pin "29") (pinfunction "PA8/T1C1/MCO_29") (pintype "passive"))
    )
    (net (code "75") (name "unconnected-(U1-PA9{slash}T1C2{slash}USART1_Tx-Pad30)") (class "Default")
      (node (ref "U1") (pin "30") (pinfunction "PA9/T1C2/USART1_Tx_30") (pintype "passive"))
    )
    (net (code "76") (name "unconnected-(U1-PA10{slash}T1C3{slash}USART1_Rx-Pad31)") (class "Default")
      (node (ref "U1") (pin "31") (pinfunction "PA10/T1C3/USART1_Rx_31") (pintype "passive"))
    )
    (net (code "77") (name "unconnected-(U1-PA11{slash}CAN_Rx{slash}T1C4{slash}USBDM-Pad32)") (class "Default")
      (node (ref "U1") (pin "32") (pinfunction "PA11/CAN_Rx/T1C4/USBDM_32") (pintype "passive"))
    )
    (net (code "78") (name "unconnected-(U1-PA12{slash}CAN_Tx{slash}T1ETR{slash}USBDP-Pad33)") (class "Default")
      (node (ref "U1") (pin "33") (pinfunction "PA12/CAN_Tx/T1ETR/USBDP_33") (pintype "passive"))
    )
    (net (code "79") (name "unconnected-(U1-PA15{slash}JTDI{slash}I2S3_WS{slash}JTDI{slash}T2C1ETR{slash}SPI3_NSS-Pad38)") (class "Default")
      (node (ref "U1") (pin "38") (pinfunction "PA15/JTDI/I2S3_WS/JTDI/T2C1ETR/SPI3_NSS_38") (pintype "passive"))
    )
    (net (code "80") (name "unconnected-(U1-PB0{slash}ADC123_IN8{slash}T3C3{slash}T8C2N{slash}T1C2N-Pad18)") (class "Default")
      (node (ref "U1") (pin "18") (pinfunction "PB0/ADC123_IN8/T3C3/T8C2N/T1C2N_18") (pintype "passive"))
    )
    (net (code "81") (name "unconnected-(U1-PB1{slash}ADC123_IN9{slash}T3C4{slash}T8C3N{slash}T1C3N-Pad19)") (class "Default")
      (node (ref "U1") (pin "19") (pinfunction "PB1/ADC123_IN9/T3C4/T8C3N/T1C3N_19") (pintype "passive"))
    )
    (net (code "82") (name "unconnected-(U1-PB3{slash}JTDO{slash}SPI3_SCK{slash}I2S3_CK{slash}T2C2{slash}SPI1_SCK-Pad39)") (class "Default")
      (node (ref "U1") (pin "39") (pinfunction "PB3/JTDO/SPI3_SCK/I2S3_CK/T2C2/SPI1_SCK_39") (pintype "passive"))
    )
    (net (code "83") (name "unconnected-(U1-PB4{slash}NJTRST{slash}SPI3_MISO{slash}T3C1{slash}SPI1_MISO-Pad40)") (class "Default")
      (node (ref "U1") (pin "40") (pinfunction "PB4/NJTRST/SPI3_MISO/T3C1/SPI1_MISO_40") (pintype "passive"))
    )
    (net (code "84") (name "unconnected-(U1-PB9{slash}SDIO_D5{slash}I2C1_SDA{slash}T4C4{slash}CAN_Tx-Pad46)") (class "Default")
      (node (ref "U1") (pin "46") (pinfunction "PB9/SDIO_D5/I2C1_SDA/T4C4/CAN_Tx_46") (pintype "passive"))
    )
    (net (code "85") (name "unconnected-(U1-PB12{slash}I2S2_WS{slash}T1BKIN{slash}SPI2_NSS{slash}I2C2_SMBA-Pad25)") (class "Default")
      (node (ref "U1") (pin "25") (pinfunction "PB12/I2S2_WS/T1BKIN/SPI2_NSS/I2C2_SMBA_25") (pintype "passive"))
    )
    (net (code "86") (name "unconnected-(U1-PB13{slash}I2S2_CK{slash}T1CH1N{slash}SPI2_SCK-Pad26)") (class "Default")
      (node (ref "U1") (pin "26") (pinfunction "PB13/I2S2_CK/T1CH1N/SPI2_SCK_26") (pintype "passive"))
    )
    (net (code "87") (name "unconnected-(U1-PB14{slash}T1CH2N{slash}SPI2_MISO-Pad27)") (class "Default")
      (node (ref "U1") (pin "27") (pinfunction "PB14/T1CH2N/SPI2_MISO_27") (pintype "passive"))
    )
    (net (code "88") (name "unconnected-(U1-PB15{slash}I2S2_SD{slash}T1CH3N{slash}SPI2_MOSI-Pad28)") (class "Default")
      (node (ref "U1") (pin "28") (pinfunction "PB15/I2S2_SD/T1CH3N/SPI2_MOSI_28") (pintype "passive"))
    )
    (net (code "89") (name "unconnected-(U1-PC13-TAMPER-RTC-Pad2)") (class "Default")
      (node (ref "U1") (pin "2") (pinfunction "PC13-TAMPER-RTC_2") (pintype "passive"))
    )
    (net (code "90") (name "unconnected-(U1-PC14-OSC32_IN-Pad3)") (class "Default")
      (node (ref "U1") (pin "3") (pinfunction "PC14-OSC32_IN_3") (pintype "passive"))
    )
    (net (code "91") (name "unconnected-(U1-PC15-OSC32_OUT-Pad4)") (class "Default")
      (node (ref "U1") (pin "4") (pinfunction "PC15-OSC32_OUT_4") (pintype "passive"))
    )
    (net (code "92") (name "unconnected-(U3-CL-Pad7)") (class "Default")
      (node (ref "U3") (pin "7") (pinfunction "CL_7") (pintype "passive"))
    )
    (net (code "93") (name "unconnected-(U3-CLKOUT-Pad22)") (class "Default")
      (node (ref "U3") (pin "22") (pinfunction "CLKOUT_22") (pintype "passive"))
    )
    (net (code "94") (name "unconnected-(U3-DA-Pad6)") (class "Default")
      (node (ref "U3") (pin "6") (pinfunction "DA_6") (pintype "passive"))
    )
    (net (code "95") (name "unconnected-(U3-INT-Pad12)") (class "Default")
      (node (ref "U3") (pin "12") (pinfunction "INT_12") (pintype "passive"))
    )
    (net (code "96") (name "unconnected-(U3-NC-Pad2)") (class "Default")
      (node (ref "U3") (pin "2") (pinfunction "NC_2") (pintype "passive"))
    )
    (net (code "97") (name "unconnected-(U3-NC-Pad3)") (class "Default")
      (node (ref "U3") (pin "3") (pinfunction "NC_3") (pintype "passive"))
    )
    (net (code "98") (name "unconnected-(U3-NC-Pad4)") (class "Default")
      (node (ref "U3") (pin "4") (pinfunction "NC_4") (pintype "passive"))
    )
    (net (code "99") (name "unconnected-(U3-NC-Pad5)") (class "Default")
      (node (ref "U3") (pin "5") (pinfunction "NC_5") (pintype "passive"))
    )
    (net (code "100") (name "unconnected-(U3-NC-Pad14)") (class "Default")
      (node (ref "U3") (pin "14") (pinfunction "NC_14") (pintype "passive"))
    )
    (net (code "101") (name "unconnected-(U3-NC-Pad15)") (class "Default")
      (node (ref "U3") (pin "15") (pinfunction "NC_15") (pintype "passive"))
    )
    (net (code "102") (name "unconnected-(U3-NC-Pad16)") (class "Default")
      (node (ref "U3") (pin "16") (pinfunction "NC_16") (pintype "passive"))
    )
    (net (code "103") (name "unconnected-(U3-NC-Pad17)") (class "Default")
      (node (ref "U3") (pin "17") (pinfunction "NC_17") (pintype "passive"))
    )
    (net (code "104") (name "unconnected-(U3-RESV-Pad19)") (class "Default")
      (node (ref "U3") (pin "19") (pinfunction "RESV_19") (pintype "passive"))
    )
    (net (code "105") (name "unconnected-(U3-RESV-Pad21)") (class "Default")
      (node (ref "U3") (pin "21") (pinfunction "RESV_21") (pintype "passive"))
    )
    (net (code "106") (name "unconnected-(U6-TEMP-Pad1)") (class "Default")
      (node (ref "U6") (pin "1") (pinfunction "TEMP_1") (pintype "passive"))
    )
  )
)
